# motherboard.net
KiCad netlist of a schematic drawn in EAGLE
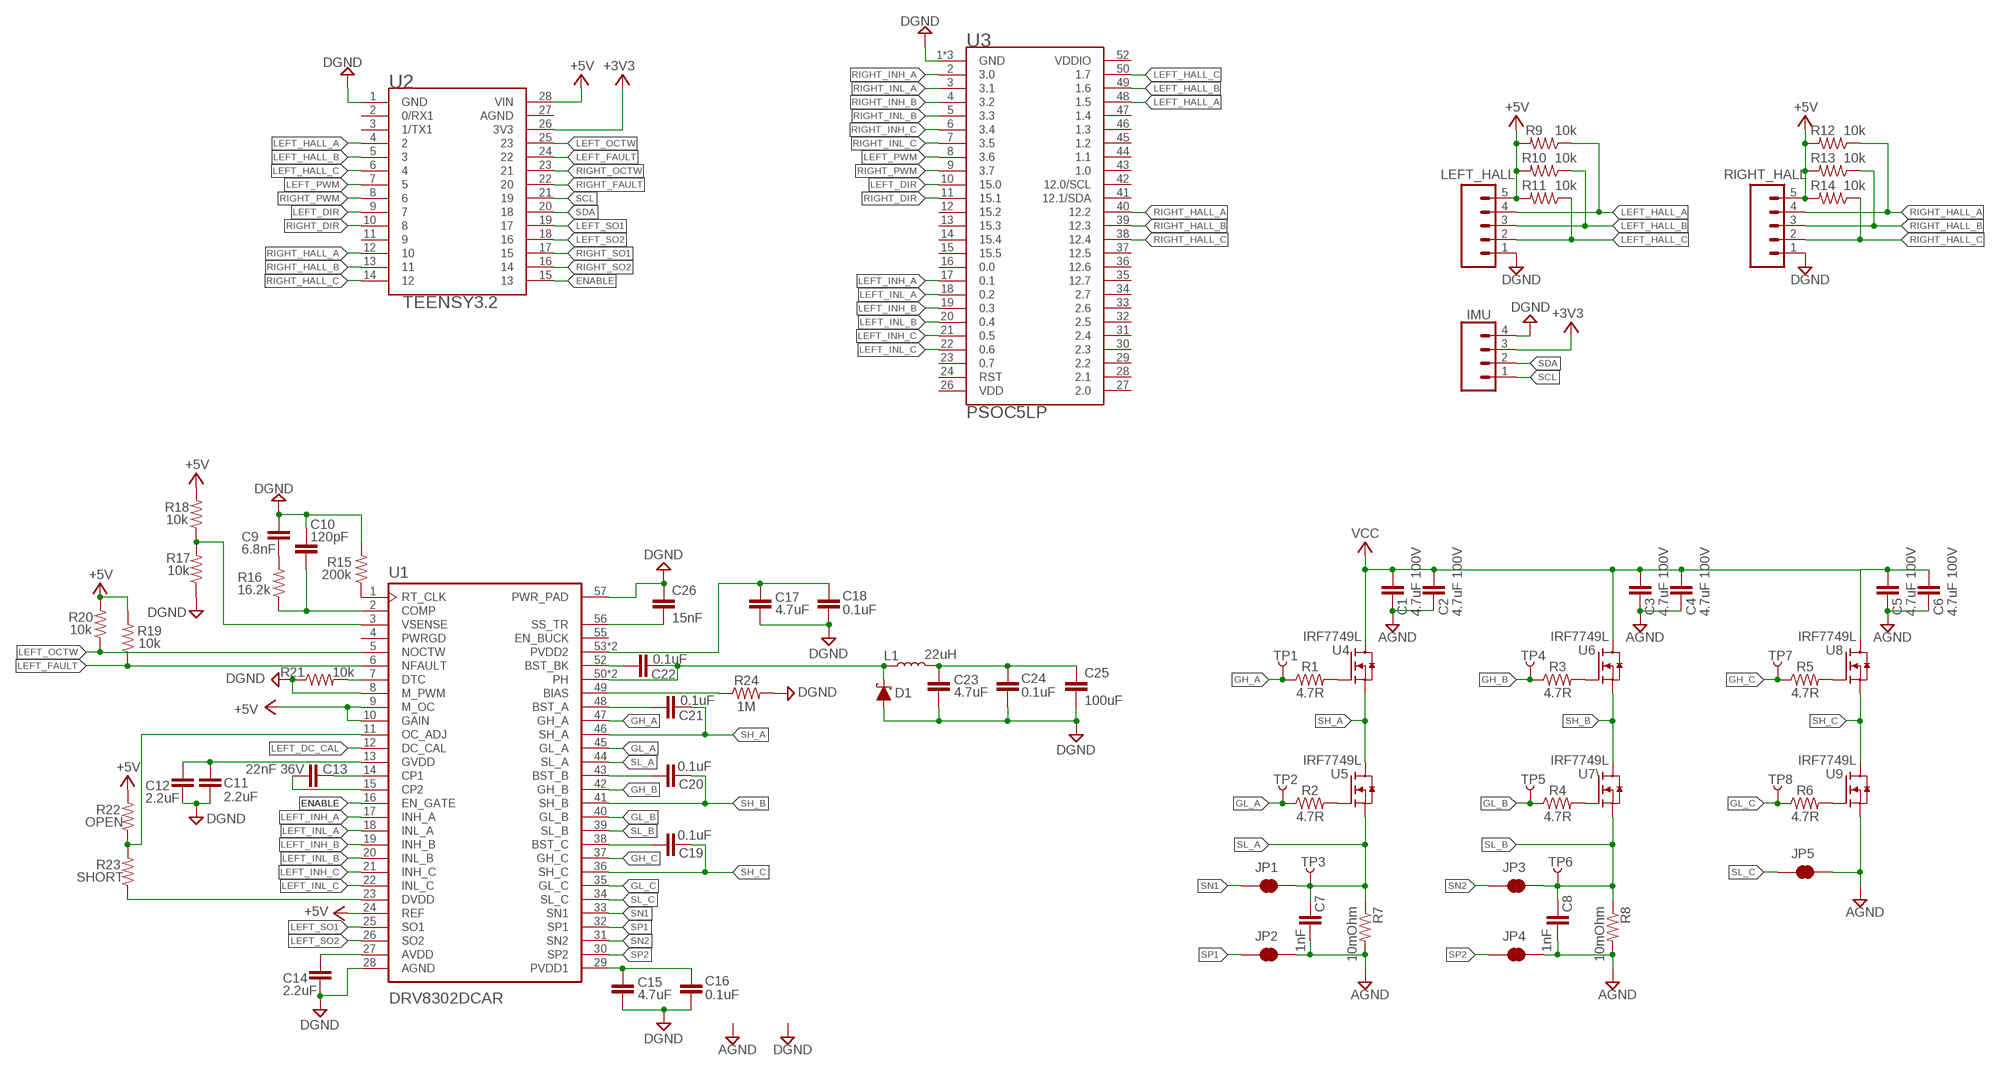
[diagram p0: schematic, sheet 1]

(export (version "E")
  (design (tool "Eeschema 10.0.6"))
  (components
    (comp (ref "C1")
      (value "4.7uF 100V")
      (footprint "eagle-import:1210")
      (libsource (lib "eagle-import") (part "10UF-1210-50V-20%"))
    )
    (comp (ref "C2")
      (value "4.7uF 100V")
      (footprint "eagle-import:1210")
      (libsource (lib "eagle-import") (part "10UF-1210-50V-20%"))
    )
    (comp (ref "C3")
      (value "4.7uF 100V")
      (footprint "eagle-import:1210")
      (libsource (lib "eagle-import") (part "10UF-1210-50V-20%"))
    )
    (comp (ref "C4")
      (value "4.7uF 100V")
      (footprint "eagle-import:1210")
      (libsource (lib "eagle-import") (part "10UF-1210-50V-20%"))
    )
    (comp (ref "C5")
      (value "4.7uF 100V")
      (footprint "eagle-import:1210")
      (libsource (lib "eagle-import") (part "10UF-1210-50V-20%"))
    )
    (comp (ref "C6")
      (value "4.7uF 100V")
      (footprint "eagle-import:1210")
      (libsource (lib "eagle-import") (part "10UF-1210-50V-20%"))
    )
    (comp (ref "C7")
      (value "1nF")
      (footprint "eagle-import:0603")
      (libsource (lib "eagle-import") (part "1.0NF/1000PF-0603-50V-10%"))
    )
    (comp (ref "C8")
      (value "1nF")
      (footprint "eagle-import:0603")
      (libsource (lib "eagle-import") (part "1.0NF/1000PF-0603-50V-10%"))
    )
    (comp (ref "C9")
      (value "6.8nF")
      (footprint "eagle-import:0603")
      (libsource (lib "eagle-import") (part "100PF-0603-50V-5%"))
    )
    (comp (ref "C10")
      (value "120pF")
      (footprint "eagle-import:0603")
      (libsource (lib "eagle-import") (part "100PF-0603-50V-5%"))
    )
    (comp (ref "C11")
      (value "2.2uF")
      (footprint "eagle-import:0805")
      (libsource (lib "eagle-import") (part "2.2UF-0805-25V-(+80/-20%)"))
    )
    (comp (ref "C12")
      (value "2.2uF")
      (footprint "eagle-import:0805")
      (libsource (lib "eagle-import") (part "2.2UF-0805-25V-(+80/-20%)"))
    )
    (comp (ref "C13")
      (value "22nF 36V")
      (footprint "eagle-import:0603")
      (libsource (lib "eagle-import") (part "22NF/22,000PF-0603-50V-10%"))
    )
    (comp (ref "C14")
      (value "2.2uF")
      (footprint "eagle-import:0805")
      (libsource (lib "eagle-import") (part "2.2UF-0805-25V-(+80/-20%)"))
    )
    (comp (ref "C15")
      (value "4.7uF")
      (footprint "eagle-import:0603")
      (libsource (lib "eagle-import") (part "4.7UF-0603-35V-(20%)"))
    )
    (comp (ref "C16")
      (value "0.1uF")
      (footprint "eagle-import:0603")
      (libsource (lib "eagle-import") (part "0.1UF-0603-25V-(+80/-20%)"))
    )
    (comp (ref "C17")
      (value "4.7uF")
      (footprint "eagle-import:0603")
      (libsource (lib "eagle-import") (part "4.7UF-0603-35V-(20%)"))
    )
    (comp (ref "C18")
      (value "0.1uF")
      (footprint "eagle-import:0603")
      (libsource (lib "eagle-import") (part "0.1UF-0603-25V-(+80/-20%)"))
    )
    (comp (ref "C19")
      (value "0.1uF")
      (footprint "eagle-import:0603")
      (libsource (lib "eagle-import") (part "0.1UF-0603-25V-(+80/-20%)"))
    )
    (comp (ref "C20")
      (value "0.1uF")
      (footprint "eagle-import:0603")
      (libsource (lib "eagle-import") (part "0.1UF-0603-25V-(+80/-20%)"))
    )
    (comp (ref "C21")
      (value "0.1uF")
      (footprint "eagle-import:0603")
      (libsource (lib "eagle-import") (part "0.1UF-0603-25V-(+80/-20%)"))
    )
    (comp (ref "C22")
      (value "0.1uF")
      (footprint "eagle-import:0603")
      (libsource (lib "eagle-import") (part "0.1UF-0603-25V-(+80/-20%)"))
    )
    (comp (ref "C23")
      (value "4.7uF")
      (footprint "eagle-import:0603")
      (libsource (lib "eagle-import") (part "4.7UF-0603-35V-(20%)"))
    )
    (comp (ref "C24")
      (value "0.1uF")
      (footprint "eagle-import:0603")
      (libsource (lib "eagle-import") (part "0.1UF-0603-25V-(+80/-20%)"))
    )
    (comp (ref "C25")
      (value "100uF")
      (footprint "eagle-import:1210")
      (libsource (lib "eagle-import") (part "100UF6.3V20%(1210)"))
    )
    (comp (ref "C26")
      (value "15nF")
      (footprint "eagle-import:0603")
      (libsource (lib "eagle-import") (part "10NF-0603-50V-10%"))
    )
    (comp (ref "D1")
      (value "NRVBA2H100T3G")
      (footprint "eagle-import:SMA-DIODE")
      (libsource (lib "eagle-import") (part "DIODE-SCHOTTKY-SS14"))
    )
    (comp (ref "IMU")
      (value "SSM-104-L-SV")
      (footprint "eagle-import:SAMTEC-SSM-104-X-SV")
      (libsource (lib "eagle-import") (part "SSM-104-L-SV"))
    )
    (comp (ref "JP1")
      (value "JUMPER-SMT_2_NC_TRACE_NO-SILK")
      (footprint "eagle-import:SMT-JUMPER_2_NC_TRACE_NO-SILK")
      (libsource (lib "eagle-import") (part "JUMPER-SMT_2_NC_TRACE_NO-SILK"))
    )
    (comp (ref "JP2")
      (value "JUMPER-SMT_2_NC_TRACE_NO-SILK")
      (footprint "eagle-import:SMT-JUMPER_2_NC_TRACE_NO-SILK")
      (libsource (lib "eagle-import") (part "JUMPER-SMT_2_NC_TRACE_NO-SILK"))
    )
    (comp (ref "JP3")
      (value "JUMPER-SMT_2_NC_TRACE_NO-SILK")
      (footprint "eagle-import:SMT-JUMPER_2_NC_TRACE_NO-SILK")
      (libsource (lib "eagle-import") (part "JUMPER-SMT_2_NC_TRACE_NO-SILK"))
    )
    (comp (ref "JP4")
      (value "JUMPER-SMT_2_NC_TRACE_NO-SILK")
      (footprint "eagle-import:SMT-JUMPER_2_NC_TRACE_NO-SILK")
      (libsource (lib "eagle-import") (part "JUMPER-SMT_2_NC_TRACE_NO-SILK"))
    )
    (comp (ref "JP5")
      (value "JUMPER-SMT_2_NC_TRACE_NO-SILK")
      (footprint "eagle-import:SMT-JUMPER_2_NC_TRACE_NO-SILK")
      (libsource (lib "eagle-import") (part "JUMPER-SMT_2_NC_TRACE_NO-SILK"))
    )
    (comp (ref "L1")
      (value "22uH")
      (footprint "eagle-import:LQH43")
      (libsource (lib "eagle-import") (part "LQH43MN330J03L"))
    )
    (comp (ref "LEFT_HALL")
      (value "CONN_05")
      (footprint "eagle-import:1X05")
      (libsource (lib "eagle-import") (part "CONN_05"))
    )
    (comp (ref "R1")
      (value "4.7R")
      (footprint "eagle-import:0603")
      (libsource (lib "eagle-import") (part "2.0KOHM-0603-1/10W-5%"))
    )
    (comp (ref "R2")
      (value "4.7R")
      (footprint "eagle-import:0603")
      (libsource (lib "eagle-import") (part "2.0KOHM-0603-1/10W-5%"))
    )
    (comp (ref "R3")
      (value "4.7R")
      (footprint "eagle-import:0603")
      (libsource (lib "eagle-import") (part "2.0KOHM-0603-1/10W-5%"))
    )
    (comp (ref "R4")
      (value "4.7R")
      (footprint "eagle-import:0603")
      (libsource (lib "eagle-import") (part "2.0KOHM-0603-1/10W-5%"))
    )
    (comp (ref "R5")
      (value "4.7R")
      (footprint "eagle-import:0603")
      (libsource (lib "eagle-import") (part "2.0KOHM-0603-1/10W-5%"))
    )
    (comp (ref "R6")
      (value "4.7R")
      (footprint "eagle-import:0603")
      (libsource (lib "eagle-import") (part "2.0KOHM-0603-1/10W-5%"))
    )
    (comp (ref "R7")
      (value "10mOhm")
      (footprint "eagle-import:R2512")
      (libsource (lib "eagle-import") (part "R-US_R2512"))
    )
    (comp (ref "R8")
      (value "10mOhm")
      (footprint "eagle-import:R2512")
      (libsource (lib "eagle-import") (part "R-US_R2512"))
    )
    (comp (ref "R9")
      (value "10k")
      (footprint "eagle-import:0603")
      (libsource (lib "eagle-import") (part "10KOHM-0603-1/10W-1%"))
    )
    (comp (ref "R10")
      (value "10k")
      (footprint "eagle-import:0603")
      (libsource (lib "eagle-import") (part "10KOHM-0603-1/10W-1%"))
    )
    (comp (ref "R11")
      (value "10k")
      (footprint "eagle-import:0603")
      (libsource (lib "eagle-import") (part "10KOHM-0603-1/10W-1%"))
    )
    (comp (ref "R12")
      (value "10k")
      (footprint "eagle-import:0603")
      (libsource (lib "eagle-import") (part "10KOHM-0603-1/10W-1%"))
    )
    (comp (ref "R13")
      (value "10k")
      (footprint "eagle-import:0603")
      (libsource (lib "eagle-import") (part "10KOHM-0603-1/10W-1%"))
    )
    (comp (ref "R14")
      (value "10k")
      (footprint "eagle-import:0603")
      (libsource (lib "eagle-import") (part "10KOHM-0603-1/10W-1%"))
    )
    (comp (ref "R15")
      (value "200k")
      (footprint "eagle-import:0603")
      (libsource (lib "eagle-import") (part "200KOHM-0603-1/10W-1%"))
    )
    (comp (ref "R16")
      (value "16.2k")
      (footprint "eagle-import:0603")
      (libsource (lib "eagle-import") (part "16.2KOHM-0603-1/10W-1%"))
    )
    (comp (ref "R17")
      (value "10k")
      (footprint "eagle-import:0603")
      (libsource (lib "eagle-import") (part "10KOHM-0603-1/10W-1%"))
    )
    (comp (ref "R18")
      (value "10k")
      (footprint "eagle-import:0603")
      (libsource (lib "eagle-import") (part "10KOHM-0603-1/10W-1%"))
    )
    (comp (ref "R19")
      (value "10k")
      (footprint "eagle-import:0603")
      (libsource (lib "eagle-import") (part "10KOHM-0603-1/10W-1%"))
    )
    (comp (ref "R20")
      (value "10k")
      (footprint "eagle-import:0603")
      (libsource (lib "eagle-import") (part "10KOHM-0603-1/10W-1%"))
    )
    (comp (ref "R21")
      (value "10k")
      (footprint "eagle-import:0603")
      (libsource (lib "eagle-import") (part "10KOHM-0603-1/10W-1%"))
    )
    (comp (ref "R22")
      (value "OPEN")
      (footprint "eagle-import:0603")
      (libsource (lib "eagle-import") (part "10KOHM-0603-1/10W-1%"))
    )
    (comp (ref "R23")
      (value "SHORT")
      (footprint "eagle-import:0603")
      (libsource (lib "eagle-import") (part "10KOHM-0603-1/10W-1%"))
    )
    (comp (ref "R24")
      (value "1M")
      (footprint "eagle-import:0603")
      (libsource (lib "eagle-import") (part "1MOHM-0603-1/4W-5%"))
    )
    (comp (ref "RIGHT_HALL")
      (value "CONN_05")
      (footprint "eagle-import:1X05")
      (libsource (lib "eagle-import") (part "CONN_05"))
    )
    (comp (ref "TP1")
      (value "TEST-POINT3")
      (footprint "eagle-import:PAD.03X.03")
      (libsource (lib "eagle-import") (part "TEST-POINT3"))
    )
    (comp (ref "TP2")
      (value "TEST-POINT3")
      (footprint "eagle-import:PAD.03X.03")
      (libsource (lib "eagle-import") (part "TEST-POINT3"))
    )
    (comp (ref "TP3")
      (value "TEST-POINT3")
      (footprint "eagle-import:PAD.03X.03")
      (libsource (lib "eagle-import") (part "TEST-POINT3"))
    )
    (comp (ref "TP4")
      (value "TEST-POINT3")
      (footprint "eagle-import:PAD.03X.03")
      (libsource (lib "eagle-import") (part "TEST-POINT3"))
    )
    (comp (ref "TP5")
      (value "TEST-POINT3")
      (footprint "eagle-import:PAD.03X.03")
      (libsource (lib "eagle-import") (part "TEST-POINT3"))
    )
    (comp (ref "TP6")
      (value "TEST-POINT3")
      (footprint "eagle-import:PAD.03X.03")
      (libsource (lib "eagle-import") (part "TEST-POINT3"))
    )
    (comp (ref "TP7")
      (value "TEST-POINT3")
      (footprint "eagle-import:PAD.03X.03")
      (libsource (lib "eagle-import") (part "TEST-POINT3"))
    )
    (comp (ref "TP8")
      (value "TEST-POINT3")
      (footprint "eagle-import:PAD.03X.03")
      (libsource (lib "eagle-import") (part "TEST-POINT3"))
    )
    (comp (ref "U1")
      (value "DRV8302DCAR")
      (footprint "eagle-import:SOP50P810X120-57N")
      (fields (field (name "MF") "Texas Instruments"))
      (libsource (lib "eagle-import") (part "DRV8302DCAR"))
    )
    (comp (ref "U2")
      (value "TEENSY3.2")
      (footprint "eagle-import:TEENSY3.2")
      (libsource (lib "eagle-import") (part "TEENSY3.2"))
    )
    (comp (ref "U3")
      (value "PSOC5LP")
      (footprint "eagle-import:PSOC5LP")
      (libsource (lib "eagle-import") (part "PSOC5LP"))
    )
    (comp (ref "U4")
      (value "IRF7749L")
      (footprint "eagle-import:TRANS_AUIRF8739L2TR")
      (libsource (lib "eagle-import") (part "IRF7749L"))
    )
    (comp (ref "U5")
      (value "IRF7749L")
      (footprint "eagle-import:TRANS_AUIRF8739L2TR")
      (libsource (lib "eagle-import") (part "IRF7749L"))
    )
    (comp (ref "U6")
      (value "IRF7749L")
      (footprint "eagle-import:TRANS_AUIRF8739L2TR")
      (libsource (lib "eagle-import") (part "IRF7749L"))
    )
    (comp (ref "U7\\")
      (value "IRF7749L")
      (footprint "eagle-import:TRANS_AUIRF8739L2TR")
      (libsource (lib "eagle-import") (part "IRF7749L"))
    )
    (comp (ref "U8")
      (value "IRF7749L")
      (footprint "eagle-import:TRANS_AUIRF8739L2TR")
      (libsource (lib "eagle-import") (part "IRF7749L"))
    )
    (comp (ref "U9")
      (value "IRF7749L")
      (footprint "eagle-import:TRANS_AUIRF8739L2TR")
      (libsource (lib "eagle-import") (part "IRF7749L"))
    )
  )
  (nets
    (net (code "1") (name "+3V3") (class "Default")
      (node (ref "IMU") (pin "3") (pinfunction "3_3") (pintype "passive"))
      (node (ref "U2") (pin "26") (pinfunction "3V3_26") (pintype "bidirectional"))
    )
    (net (code "2") (name "+5V") (class "Default")
      (node (ref "LEFT_HALL") (pin "5") (pinfunction "5_5") (pintype "passive"))
      (node (ref "R10") (pin "2") (pinfunction "2_2") (pintype "passive"))
      (node (ref "R11") (pin "2") (pinfunction "2_2") (pintype "passive"))
      (node (ref "R12") (pin "2") (pinfunction "2_2") (pintype "passive"))
      (node (ref "R13") (pin "2") (pinfunction "2_2") (pintype "passive"))
      (node (ref "R14") (pin "2") (pinfunction "2_2") (pintype "passive"))
      (node (ref "R18") (pin "2") (pinfunction "2_2") (pintype "passive"))
      (node (ref "R19") (pin "2") (pinfunction "2_2") (pintype "passive"))
      (node (ref "R20") (pin "2") (pinfunction "2_2") (pintype "passive"))
      (node (ref "R22") (pin "2") (pinfunction "2_2") (pintype "passive"))
      (node (ref "R9") (pin "2") (pinfunction "2_2") (pintype "passive"))
      (node (ref "RIGHT_HALL") (pin "5") (pinfunction "5_5") (pintype "passive"))
      (node (ref "U1") (pin "10") (pinfunction "GAIN_10") (pintype "output"))
      (node (ref "U1") (pin "24") (pinfunction "REF_24") (pintype "input"))
      (node (ref "U1") (pin "9") (pinfunction "M_OC_9") (pintype "input"))
      (node (ref "U2") (pin "28") (pinfunction "VIN_28") (pintype "bidirectional"))
    )
    (net (code "3") (name "AGND") (class "Default")
      (node (ref "C1") (pin "2") (pinfunction "2_2") (pintype "passive"))
      (node (ref "C2") (pin "2") (pinfunction "2_2") (pintype "passive"))
      (node (ref "C3") (pin "2") (pinfunction "2_2") (pintype "passive"))
      (node (ref "C4") (pin "2") (pinfunction "2_2") (pintype "passive"))
      (node (ref "C5") (pin "2") (pinfunction "2_2") (pintype "passive"))
      (node (ref "C6") (pin "2") (pinfunction "2_2") (pintype "passive"))
      (node (ref "C7") (pin "2") (pinfunction "2_2") (pintype "passive"))
      (node (ref "C8") (pin "2") (pinfunction "2_2") (pintype "passive"))
      (node (ref "JP2") (pin "2") (pinfunction "2_2") (pintype "passive"))
      (node (ref "JP4") (pin "2") (pinfunction "2_2") (pintype "passive"))
      (node (ref "JP5") (pin "2") (pinfunction "2_2") (pintype "passive"))
      (node (ref "R7") (pin "2") (pinfunction "2_2") (pintype "passive"))
      (node (ref "R8") (pin "2") (pinfunction "2_2") (pintype "passive"))
      (node (ref "U9") (pin "10") (pinfunction "S_10") (pintype "passive"))
      (node (ref "U9") (pin "11") (pinfunction "S_11") (pintype "passive"))
      (node (ref "U9") (pin "4") (pinfunction "S_4") (pintype "passive"))
      (node (ref "U9") (pin "5") (pinfunction "S_5") (pintype "passive"))
      (node (ref "U9") (pin "6") (pinfunction "S_6") (pintype "passive"))
      (node (ref "U9") (pin "7") (pinfunction "S_7") (pintype "passive"))
      (node (ref "U9") (pin "8") (pinfunction "S_8") (pintype "passive"))
      (node (ref "U9") (pin "9") (pinfunction "S_9") (pintype "passive"))
    )
    (net (code "4") (name "DGND") (class "Default")
      (node (ref "C10") (pin "1") (pinfunction "1_1") (pintype "passive"))
      (node (ref "C11") (pin "2") (pinfunction "2_2") (pintype "passive"))
      (node (ref "C12") (pin "2") (pinfunction "2_2") (pintype "passive"))
      (node (ref "C14") (pin "2") (pinfunction "2_2") (pintype "passive"))
      (node (ref "C15") (pin "2") (pinfunction "2_2") (pintype "passive"))
      (node (ref "C16") (pin "2") (pinfunction "2_2") (pintype "passive"))
      (node (ref "C17") (pin "2") (pinfunction "2_2") (pintype "passive"))
      (node (ref "C18") (pin "2") (pinfunction "2_2") (pintype "passive"))
      (node (ref "C23") (pin "2") (pinfunction "2_2") (pintype "passive"))
      (node (ref "C24") (pin "2") (pinfunction "2_2") (pintype "passive"))
      (node (ref "C25") (pin "2") (pinfunction "2_2") (pintype "passive"))
      (node (ref "C26") (pin "1") (pinfunction "1_1") (pintype "passive"))
      (node (ref "C9") (pin "1") (pinfunction "1_1") (pintype "passive"))
      (node (ref "D1") (pin "A") (pinfunction "A_A") (pintype "passive"))
      (node (ref "IMU") (pin "4") (pinfunction "4_4") (pintype "passive"))
      (node (ref "LEFT_HALL") (pin "1") (pinfunction "1_1") (pintype "passive"))
      (node (ref "R15") (pin "2") (pinfunction "2_2") (pintype "passive"))
      (node (ref "R17") (pin "1") (pinfunction "1_1") (pintype "passive"))
      (node (ref "R21") (pin "1") (pinfunction "1_1") (pintype "passive"))
      (node (ref "R24") (pin "2") (pinfunction "2_2") (pintype "passive"))
      (node (ref "RIGHT_HALL") (pin "1") (pinfunction "1_1") (pintype "passive"))
      (node (ref "U1") (pin "28") (pinfunction "AGND_28") (pintype "power_in"))
      (node (ref "U1") (pin "57") (pinfunction "PWR_PAD_57") (pintype "power_in"))
      (node (ref "U1") (pin "8") (pinfunction "M_PWM_8") (pintype "input"))
      (node (ref "U2") (pin "1") (pinfunction "GND_1") (pintype "bidirectional"))
      (node (ref "U3") (pin "1") (pinfunction "GND_1") (pintype "bidirectional"))
      (node (ref "U3") (pin "25") (pinfunction "GND_25") (pintype "bidirectional"))
      (node (ref "U3") (pin "51") (pinfunction "GND_51") (pintype "bidirectional"))
    )
    (net (code "5") (name "ENABLE") (class "Default")
      (node (ref "U1") (pin "16") (pinfunction "EN_GATE_16") (pintype "input"))
      (node (ref "U2") (pin "15") (pinfunction "13_15") (pintype "bidirectional"))
    )
    (net (code "6") (name "GH_A") (class "Default")
      (node (ref "R1") (pin "1") (pinfunction "1_1") (pintype "passive"))
      (node (ref "TP1") (pin "P$1") (pinfunction "1_P$1") (pintype "bidirectional"))
      (node (ref "U1") (pin "47") (pinfunction "GH_A_47") (pintype "output"))
    )
    (net (code "7") (name "GH_B") (class "Default")
      (node (ref "R3") (pin "1") (pinfunction "1_1") (pintype "passive"))
      (node (ref "TP4") (pin "P$1") (pinfunction "1_P$1") (pintype "bidirectional"))
      (node (ref "U1") (pin "42") (pinfunction "GH_B_42") (pintype "output"))
    )
    (net (code "8") (name "GH_C") (class "Default")
      (node (ref "R5") (pin "1") (pinfunction "1_1") (pintype "passive"))
      (node (ref "TP7") (pin "P$1") (pinfunction "1_P$1") (pintype "bidirectional"))
      (node (ref "U1") (pin "37") (pinfunction "GH_C_37") (pintype "output"))
    )
    (net (code "9") (name "GL_A") (class "Default")
      (node (ref "R2") (pin "1") (pinfunction "1_1") (pintype "passive"))
      (node (ref "TP2") (pin "P$1") (pinfunction "1_P$1") (pintype "bidirectional"))
      (node (ref "U1") (pin "45") (pinfunction "GL_A_45") (pintype "output"))
    )
    (net (code "10") (name "GL_B") (class "Default")
      (node (ref "R4") (pin "1") (pinfunction "1_1") (pintype "passive"))
      (node (ref "TP5") (pin "P$1") (pinfunction "1_P$1") (pintype "bidirectional"))
      (node (ref "U1") (pin "40") (pinfunction "GL_B_40") (pintype "output"))
    )
    (net (code "11") (name "GL_C") (class "Default")
      (node (ref "R6") (pin "1") (pinfunction "1_1") (pintype "passive"))
      (node (ref "TP8") (pin "P$1") (pinfunction "1_P$1") (pintype "bidirectional"))
      (node (ref "U1") (pin "35") (pinfunction "GL_C_35") (pintype "output"))
    )
    (net (code "12") (name "LEFT_DC_CAL") (class "Default")
      (node (ref "U1") (pin "12") (pinfunction "DC_CAL_12") (pintype "input"))
    )
    (net (code "13") (name "LEFT_DIR") (class "Default")
      (node (ref "U2") (pin "9") (pinfunction "7_9") (pintype "bidirectional"))
      (node (ref "U3") (pin "10") (pinfunction "15.0_10") (pintype "bidirectional"))
    )
    (net (code "14") (name "LEFT_FAULT") (class "Default")
      (node (ref "R19") (pin "1") (pinfunction "1_1") (pintype "passive"))
      (node (ref "U1") (pin "6") (pinfunction "NFAULT_6") (pintype "output"))
      (node (ref "U2") (pin "24") (pinfunction "22_24") (pintype "bidirectional"))
    )
    (net (code "15") (name "LEFT_HALL_A") (class "Default")
      (node (ref "LEFT_HALL") (pin "4") (pinfunction "4_4") (pintype "passive"))
      (node (ref "R9") (pin "1") (pinfunction "1_1") (pintype "passive"))
      (node (ref "U2") (pin "4") (pinfunction "2_4") (pintype "bidirectional"))
      (node (ref "U3") (pin "48") (pinfunction "1.5_48") (pintype "bidirectional"))
    )
    (net (code "16") (name "LEFT_HALL_B") (class "Default")
      (node (ref "LEFT_HALL") (pin "3") (pinfunction "3_3") (pintype "passive"))
      (node (ref "R10") (pin "1") (pinfunction "1_1") (pintype "passive"))
      (node (ref "U2") (pin "5") (pinfunction "3_5") (pintype "bidirectional"))
      (node (ref "U3") (pin "49") (pinfunction "1.6_49") (pintype "bidirectional"))
    )
    (net (code "17") (name "LEFT_HALL_C") (class "Default")
      (node (ref "LEFT_HALL") (pin "2") (pinfunction "2_2") (pintype "passive"))
      (node (ref "R11") (pin "1") (pinfunction "1_1") (pintype "passive"))
      (node (ref "U2") (pin "6") (pinfunction "4_6") (pintype "bidirectional"))
      (node (ref "U3") (pin "50") (pinfunction "1.7_50") (pintype "bidirectional"))
    )
    (net (code "18") (name "LEFT_INH_A") (class "Default")
      (node (ref "U1") (pin "17") (pinfunction "INH_A_17") (pintype "input"))
      (node (ref "U3") (pin "17") (pinfunction "0.1_17") (pintype "bidirectional"))
    )
    (net (code "19") (name "LEFT_INH_B") (class "Default")
      (node (ref "U1") (pin "19") (pinfunction "INH_B_19") (pintype "input"))
      (node (ref "U3") (pin "19") (pinfunction "0.3_19") (pintype "bidirectional"))
    )
    (net (code "20") (name "LEFT_INH_C") (class "Default")
      (node (ref "U1") (pin "21") (pinfunction "INH_C_21") (pintype "input"))
      (node (ref "U3") (pin "21") (pinfunction "0.5_21") (pintype "bidirectional"))
    )
    (net (code "21") (name "LEFT_INL_A") (class "Default")
      (node (ref "U1") (pin "18") (pinfunction "INL_A_18") (pintype "input"))
      (node (ref "U3") (pin "18") (pinfunction "0.2_18") (pintype "bidirectional"))
    )
    (net (code "22") (name "LEFT_INL_B") (class "Default")
      (node (ref "U1") (pin "20") (pinfunction "INL_B_20") (pintype "input"))
      (node (ref "U3") (pin "20") (pinfunction "0.4_20") (pintype "bidirectional"))
    )
    (net (code "23") (name "LEFT_INL_C") (class "Default")
      (node (ref "U1") (pin "22") (pinfunction "INL_C_22") (pintype "input"))
      (node (ref "U3") (pin "22") (pinfunction "0.6_22") (pintype "bidirectional"))
    )
    (net (code "24") (name "LEFT_OCTW") (class "Default")
      (node (ref "R20") (pin "1") (pinfunction "1_1") (pintype "passive"))
      (node (ref "U1") (pin "5") (pinfunction "NOCTW_5") (pintype "output"))
      (node (ref "U2") (pin "25") (pinfunction "23_25") (pintype "bidirectional"))
    )
    (net (code "25") (name "LEFT_PWM") (class "Default")
      (node (ref "U2") (pin "7") (pinfunction "5_7") (pintype "bidirectional"))
      (node (ref "U3") (pin "8") (pinfunction "3.6_8") (pintype "bidirectional"))
    )
    (net (code "26") (name "LEFT_SO1") (class "Default")
      (node (ref "U1") (pin "25") (pinfunction "SO1_25") (pintype "output"))
      (node (ref "U2") (pin "19") (pinfunction "17_19") (pintype "bidirectional"))
    )
    (net (code "27") (name "LEFT_SO2") (class "Default")
      (node (ref "U1") (pin "26") (pinfunction "SO2_26") (pintype "output"))
      (node (ref "U2") (pin "18") (pinfunction "16_18") (pintype "bidirectional"))
    )
    (net (code "28") (name "Net-(C9-Pad2)") (class "Default")
      (node (ref "C9") (pin "2") (pinfunction "2_2") (pintype "passive"))
      (node (ref "R16") (pin "2") (pinfunction "2_2") (pintype "passive"))
    )
    (net (code "29") (name "Net-(C17-Pad1)") (class "Default")
      (node (ref "C17") (pin "1") (pinfunction "1_1") (pintype "passive"))
      (node (ref "C18") (pin "1") (pinfunction "1_1") (pintype "passive"))
      (node (ref "U1") (pin "53") (pinfunction "PVDD2_53") (pintype "power_in"))
      (node (ref "U1") (pin "54") (pinfunction "PVDD2_54") (pintype "power_in"))
    )
    (net (code "30") (name "Net-(C22-Pad1)") (class "Default")
      (node (ref "C22") (pin "1") (pinfunction "1_1") (pintype "passive"))
      (node (ref "D1") (pin "C") (pinfunction "C_C") (pintype "passive"))
      (node (ref "L1") (pin "1") (pinfunction "1_1") (pintype "passive"))
      (node (ref "U1") (pin "50") (pinfunction "PH_50") (pintype "bidirectional"))
      (node (ref "U1") (pin "51") (pinfunction "PH_51") (pintype "bidirectional"))
    )
    (net (code "31") (name "Net-(C23-Pad1)") (class "Default")
      (node (ref "C23") (pin "1") (pinfunction "1_1") (pintype "passive"))
      (node (ref "C24") (pin "1") (pinfunction "1_1") (pintype "passive"))
      (node (ref "C25") (pin "1") (pinfunction "1_1") (pintype "passive"))
      (node (ref "L1") (pin "2") (pinfunction "2_2") (pintype "passive"))
    )
    (net (code "32") (name "Net-(U1-AVDD)") (class "Default")
      (node (ref "C14") (pin "1") (pinfunction "1_1") (pintype "passive"))
      (node (ref "U1") (pin "27") (pinfunction "AVDD_27") (pintype "power_in"))
    )
    (net (code "33") (name "Net-(U1-BIAS)") (class "Default")
      (node (ref "R24") (pin "1") (pinfunction "1_1") (pintype "passive"))
      (node (ref "U1") (pin "49") (pinfunction "BIAS_49") (pintype "input"))
    )
    (net (code "34") (name "Net-(U1-BST_A)") (class "Default")
      (node (ref "C21") (pin "2") (pinfunction "2_2") (pintype "passive"))
      (node (ref "U1") (pin "48") (pinfunction "BST_A_48") (pintype "power_in"))
    )
    (net (code "35") (name "Net-(U1-BST_B)") (class "Default")
      (node (ref "C20") (pin "2") (pinfunction "2_2") (pintype "passive"))
      (node (ref "U1") (pin "43") (pinfunction "BST_B_43") (pintype "power_in"))
    )
    (net (code "36") (name "Net-(U1-BST_BK)") (class "Default")
      (node (ref "C22") (pin "2") (pinfunction "2_2") (pintype "passive"))
      (node (ref "U1") (pin "52") (pinfunction "BST_BK_52") (pintype "power_in"))
    )
    (net (code "37") (name "Net-(U1-BST_C)") (class "Default")
      (node (ref "C19") (pin "2") (pinfunction "2_2") (pintype "passive"))
      (node (ref "U1") (pin "38") (pinfunction "BST_C_38") (pintype "power_in"))
    )
    (net (code "38") (name "Net-(U1-COMP)") (class "Default")
      (node (ref "C10") (pin "2") (pinfunction "2_2") (pintype "passive"))
      (node (ref "R16") (pin "1") (pinfunction "1_1") (pintype "passive"))
      (node (ref "U1") (pin "2") (pinfunction "COMP_2") (pintype "output"))
    )
    (net (code "39") (name "Net-(U1-CP1)") (class "Default")
      (node (ref "C13") (pin "1") (pinfunction "1_1") (pintype "passive"))
      (node (ref "U1") (pin "14") (pinfunction "CP1_14") (pintype "power_in"))
    )
    (net (code "40") (name "Net-(U1-CP2)") (class "Default")
      (node (ref "C13") (pin "2") (pinfunction "2_2") (pintype "passive"))
      (node (ref "U1") (pin "15") (pinfunction "CP2_15") (pintype "power_in"))
    )
    (net (code "41") (name "Net-(U1-DTC)") (class "Default")
      (node (ref "R21") (pin "2") (pinfunction "2_2") (pintype "passive"))
      (node (ref "U1") (pin "7") (pinfunction "DTC_7") (pintype "input"))
    )
    (net (code "42") (name "Net-(U1-DVDD)") (class "Default")
      (node (ref "R23") (pin "1") (pinfunction "1_1") (pintype "passive"))
      (node (ref "U1") (pin "23") (pinfunction "DVDD_23") (pintype "power_in"))
    )
    (net (code "43") (name "Net-(U1-GVDD)") (class "Default")
      (node (ref "C11") (pin "1") (pinfunction "1_1") (pintype "passive"))
      (node (ref "C12") (pin "1") (pinfunction "1_1") (pintype "passive"))
      (node (ref "U1") (pin "13") (pinfunction "GVDD_13") (pintype "power_in"))
    )
    (net (code "44") (name "Net-(U1-OC_ADJ)") (class "Default")
      (node (ref "R22") (pin "1") (pinfunction "1_1") (pintype "passive"))
      (node (ref "R23") (pin "2") (pinfunction "2_2") (pintype "passive"))
      (node (ref "U1") (pin "11") (pinfunction "OC_ADJ_11") (pintype "input"))
    )
    (net (code "45") (name "Net-(U1-PVDD1)") (class "Default")
      (node (ref "C15") (pin "1") (pinfunction "1_1") (pintype "passive"))
      (node (ref "C16") (pin "1") (pinfunction "1_1") (pintype "passive"))
      (node (ref "U1") (pin "29") (pinfunction "PVDD1_29") (pintype "power_in"))
    )
    (net (code "46") (name "Net-(U1-RT_CLK)") (class "Default")
      (node (ref "R15") (pin "1") (pinfunction "1_1") (pintype "passive"))
      (node (ref "U1") (pin "1") (pinfunction "RT_CLK_1") (pintype "input"))
    )
    (net (code "47") (name "Net-(U1-SS_TR)") (class "Default")
      (node (ref "C26") (pin "2") (pinfunction "2_2") (pintype "passive"))
      (node (ref "U1") (pin "56") (pinfunction "SS_TR_56") (pintype "input"))
    )
    (net (code "48") (name "Net-(U1-VSENSE)") (class "Default")
      (node (ref "R17") (pin "2") (pinfunction "2_2") (pintype "passive"))
      (node (ref "R18") (pin "1") (pinfunction "1_1") (pintype "passive"))
      (node (ref "U1") (pin "3") (pinfunction "VSENSE_3") (pintype "input"))
    )
    (net (code "49") (name "Net-(U4-G)") (class "Default")
      (node (ref "R1") (pin "2") (pinfunction "2_2") (pintype "passive"))
      (node (ref "U4") (pin "12") (pinfunction "G_12") (pintype "passive"))
    )
    (net (code "50") (name "Net-(U5-G)") (class "Default")
      (node (ref "R2") (pin "2") (pinfunction "2_2") (pintype "passive"))
      (node (ref "U5") (pin "12") (pinfunction "G_12") (pintype "passive"))
    )
    (net (code "51") (name "Net-(U6-G)") (class "Default")
      (node (ref "R3") (pin "2") (pinfunction "2_2") (pintype "passive"))
      (node (ref "U6") (pin "12") (pinfunction "G_12") (pintype "passive"))
    )
    (net (code "52") (name "Net-(U7\\-G)") (class "Default")
      (node (ref "R4") (pin "2") (pinfunction "2_2") (pintype "passive"))
      (node (ref "U7\\") (pin "12") (pinfunction "G_12") (pintype "passive"))
    )
    (net (code "53") (name "Net-(U8-G)") (class "Default")
      (node (ref "R5") (pin "2") (pinfunction "2_2") (pintype "passive"))
      (node (ref "U8") (pin "12") (pinfunction "G_12") (pintype "passive"))
    )
    (net (code "54") (name "Net-(U9-G)") (class "Default")
      (node (ref "R6") (pin "2") (pinfunction "2_2") (pintype "passive"))
      (node (ref "U9") (pin "12") (pinfunction "G_12") (pintype "passive"))
    )
    (net (code "55") (name "RIGHT_DIR") (class "Default")
      (node (ref "U2") (pin "10") (pinfunction "8_10") (pintype "bidirectional"))
      (node (ref "U3") (pin "11") (pinfunction "15.1_11") (pintype "bidirectional"))
    )
    (net (code "56") (name "RIGHT_FAULT") (class "Default")
      (node (ref "U2") (pin "22") (pinfunction "20_22") (pintype "bidirectional"))
    )
    (net (code "57") (name "RIGHT_HALL_A") (class "Default")
      (node (ref "R12") (pin "1") (pinfunction "1_1") (pintype "passive"))
      (node (ref "RIGHT_HALL") (pin "4") (pinfunction "4_4") (pintype "passive"))
      (node (ref "U2") (pin "12") (pinfunction "10_12") (pintype "bidirectional"))
      (node (ref "U3") (pin "40") (pinfunction "12.2_40") (pintype "bidirectional"))
    )
    (net (code "58") (name "RIGHT_HALL_B") (class "Default")
      (node (ref "R13") (pin "1") (pinfunction "1_1") (pintype "passive"))
      (node (ref "RIGHT_HALL") (pin "3") (pinfunction "3_3") (pintype "passive"))
      (node (ref "U2") (pin "13") (pinfunction "11_13") (pintype "bidirectional"))
      (node (ref "U3") (pin "39") (pinfunction "12.3_39") (pintype "bidirectional"))
    )
    (net (code "59") (name "RIGHT_HALL_C") (class "Default")
      (node (ref "R14") (pin "1") (pinfunction "1_1") (pintype "passive"))
      (node (ref "RIGHT_HALL") (pin "2") (pinfunction "2_2") (pintype "passive"))
      (node (ref "U2") (pin "14") (pinfunction "12_14") (pintype "bidirectional"))
      (node (ref "U3") (pin "38") (pinfunction "12.4_38") (pintype "bidirectional"))
    )
    (net (code "60") (name "RIGHT_INH_A") (class "Default")
      (node (ref "U3") (pin "2") (pinfunction "3.0_2") (pintype "bidirectional"))
    )
    (net (code "61") (name "RIGHT_INH_B") (class "Default")
      (node (ref "U3") (pin "4") (pinfunction "3.2_4") (pintype "bidirectional"))
    )
    (net (code "62") (name "RIGHT_INH_C") (class "Default")
      (node (ref "U3") (pin "6") (pinfunction "3.4_6") (pintype "bidirectional"))
    )
    (net (code "63") (name "RIGHT_INL_A") (class "Default")
      (node (ref "U3") (pin "3") (pinfunction "3.1_3") (pintype "bidirectional"))
    )
    (net (code "64") (name "RIGHT_INL_B") (class "Default")
      (node (ref "U3") (pin "5") (pinfunction "3.3_5") (pintype "bidirectional"))
    )
    (net (code "65") (name "RIGHT_INL_C") (class "Default")
      (node (ref "U3") (pin "7") (pinfunction "3.5_7") (pintype "bidirectional"))
    )
    (net (code "66") (name "RIGHT_OCTW") (class "Default")
      (node (ref "U2") (pin "23") (pinfunction "21_23") (pintype "bidirectional"))
    )
    (net (code "67") (name "RIGHT_PWM") (class "Default")
      (node (ref "U2") (pin "8") (pinfunction "6_8") (pintype "bidirectional"))
      (node (ref "U3") (pin "9") (pinfunction "3.7_9") (pintype "bidirectional"))
    )
    (net (code "68") (name "RIGHT_SO1") (class "Default")
      (node (ref "U2") (pin "17") (pinfunction "15_17") (pintype "bidirectional"))
    )
    (net (code "69") (name "RIGHT_SO2") (class "Default")
      (node (ref "U2") (pin "16") (pinfunction "14_16") (pintype "bidirectional"))
    )
    (net (code "70") (name "SCL") (class "Default")
      (node (ref "IMU") (pin "1") (pinfunction "1_1") (pintype "passive"))
      (node (ref "U2") (pin "21") (pinfunction "19_21") (pintype "bidirectional"))
    )
    (net (code "71") (name "SDA") (class "Default")
      (node (ref "IMU") (pin "2") (pinfunction "2_2") (pintype "passive"))
      (node (ref "U2") (pin "20") (pinfunction "18_20") (pintype "bidirectional"))
    )
    (net (code "72") (name "SH_A") (class "Default")
      (node (ref "C21") (pin "1") (pinfunction "1_1") (pintype "passive"))
      (node (ref "U1") (pin "46") (pinfunction "SH_A_46") (pintype "input"))
      (node (ref "U4") (pin "10") (pinfunction "S_10") (pintype "passive"))
      (node (ref "U4") (pin "11") (pinfunction "S_11") (pintype "passive"))
      (node (ref "U4") (pin "4") (pinfunction "S_4") (pintype "passive"))
      (node (ref "U4") (pin "5") (pinfunction "S_5") (pintype "passive"))
      (node (ref "U4") (pin "6") (pinfunction "S_6") (pintype "passive"))
      (node (ref "U4") (pin "7") (pinfunction "S_7") (pintype "passive"))
      (node (ref "U4") (pin "8") (pinfunction "S_8") (pintype "passive"))
      (node (ref "U4") (pin "9") (pinfunction "S_9") (pintype "passive"))
      (node (ref "U5") (pin "1") (pinfunction "D_1") (pintype "passive"))
      (node (ref "U5") (pin "13") (pinfunction "D_13") (pintype "passive"))
      (node (ref "U5") (pin "14") (pinfunction "D_14") (pintype "passive"))
      (node (ref "U5") (pin "15") (pinfunction "D_15") (pintype "passive"))
      (node (ref "U5") (pin "2") (pinfunction "D_2") (pintype "passive"))
      (node (ref "U5") (pin "3") (pinfunction "D_3") (pintype "passive"))
    )
    (net (code "73") (name "SH_B") (class "Default")
      (node (ref "C20") (pin "1") (pinfunction "1_1") (pintype "passive"))
      (node (ref "U1") (pin "41") (pinfunction "SH_B_41") (pintype "input"))
      (node (ref "U6") (pin "10") (pinfunction "S_10") (pintype "passive"))
      (node (ref "U6") (pin "11") (pinfunction "S_11") (pintype "passive"))
      (node (ref "U6") (pin "4") (pinfunction "S_4") (pintype "passive"))
      (node (ref "U6") (pin "5") (pinfunction "S_5") (pintype "passive"))
      (node (ref "U6") (pin "6") (pinfunction "S_6") (pintype "passive"))
      (node (ref "U6") (pin "7") (pinfunction "S_7") (pintype "passive"))
      (node (ref "U6") (pin "8") (pinfunction "S_8") (pintype "passive"))
      (node (ref "U6") (pin "9") (pinfunction "S_9") (pintype "passive"))
      (node (ref "U7\\") (pin "1") (pinfunction "D_1") (pintype "passive"))
      (node (ref "U7\\") (pin "13") (pinfunction "D_13") (pintype "passive"))
      (node (ref "U7\\") (pin "14") (pinfunction "D_14") (pintype "passive"))
      (node (ref "U7\\") (pin "15") (pinfunction "D_15") (pintype "passive"))
      (node (ref "U7\\") (pin "2") (pinfunction "D_2") (pintype "passive"))
      (node (ref "U7\\") (pin "3") (pinfunction "D_3") (pintype "passive"))
    )
    (net (code "74") (name "SH_C") (class "Default")
      (node (ref "C19") (pin "1") (pinfunction "1_1") (pintype "passive"))
      (node (ref "U1") (pin "36") (pinfunction "SH_C_36") (pintype "input"))
      (node (ref "U8") (pin "10") (pinfunction "S_10") (pintype "passive"))
      (node (ref "U8") (pin "11") (pinfunction "S_11") (pintype "passive"))
      (node (ref "U8") (pin "4") (pinfunction "S_4") (pintype "passive"))
      (node (ref "U8") (pin "5") (pinfunction "S_5") (pintype "passive"))
      (node (ref "U8") (pin "6") (pinfunction "S_6") (pintype "passive"))
      (node (ref "U8") (pin "7") (pinfunction "S_7") (pintype "passive"))
      (node (ref "U8") (pin "8") (pinfunction "S_8") (pintype "passive"))
      (node (ref "U8") (pin "9") (pinfunction "S_9") (pintype "passive"))
      (node (ref "U9") (pin "1") (pinfunction "D_1") (pintype "passive"))
      (node (ref "U9") (pin "13") (pinfunction "D_13") (pintype "passive"))
      (node (ref "U9") (pin "14") (pinfunction "D_14") (pintype "passive"))
      (node (ref "U9") (pin "15") (pinfunction "D_15") (pintype "passive"))
      (node (ref "U9") (pin "2") (pinfunction "D_2") (pintype "passive"))
      (node (ref "U9") (pin "3") (pinfunction "D_3") (pintype "passive"))
    )
    (net (code "75") (name "SL_A") (class "Default")
      (node (ref "C7") (pin "1") (pinfunction "1_1") (pintype "passive"))
      (node (ref "JP1") (pin "2") (pinfunction "2_2") (pintype "passive"))
      (node (ref "R7") (pin "1") (pinfunction "1_1") (pintype "passive"))
      (node (ref "TP3") (pin "P$1") (pinfunction "1_P$1") (pintype "bidirectional"))
      (node (ref "U1") (pin "44") (pinfunction "SL_A_44") (pintype "input"))
      (node (ref "U5") (pin "10") (pinfunction "S_10") (pintype "passive"))
      (node (ref "U5") (pin "11") (pinfunction "S_11") (pintype "passive"))
      (node (ref "U5") (pin "4") (pinfunction "S_4") (pintype "passive"))
      (node (ref "U5") (pin "5") (pinfunction "S_5") (pintype "passive"))
      (node (ref "U5") (pin "6") (pinfunction "S_6") (pintype "passive"))
      (node (ref "U5") (pin "7") (pinfunction "S_7") (pintype "passive"))
      (node (ref "U5") (pin "8") (pinfunction "S_8") (pintype "passive"))
      (node (ref "U5") (pin "9") (pinfunction "S_9") (pintype "passive"))
    )
    (net (code "76") (name "SL_B") (class "Default")
      (node (ref "C8") (pin "1") (pinfunction "1_1") (pintype "passive"))
      (node (ref "JP3") (pin "2") (pinfunction "2_2") (pintype "passive"))
      (node (ref "R8") (pin "1") (pinfunction "1_1") (pintype "passive"))
      (node (ref "TP6") (pin "P$1") (pinfunction "1_P$1") (pintype "bidirectional"))
      (node (ref "U1") (pin "39") (pinfunction "SL_B_39") (pintype "input"))
      (node (ref "U7\\") (pin "10") (pinfunction "S_10") (pintype "passive"))
      (node (ref "U7\\") (pin "11") (pinfunction "S_11") (pintype "passive"))
      (node (ref "U7\\") (pin "4") (pinfunction "S_4") (pintype "passive"))
      (node (ref "U7\\") (pin "5") (pinfunction "S_5") (pintype "passive"))
      (node (ref "U7\\") (pin "6") (pinfunction "S_6") (pintype "passive"))
      (node (ref "U7\\") (pin "7") (pinfunction "S_7") (pintype "passive"))
      (node (ref "U7\\") (pin "8") (pinfunction "S_8") (pintype "passive"))
      (node (ref "U7\\") (pin "9") (pinfunction "S_9") (pintype "passive"))
    )
    (net (code "77") (name "SL_C") (class "Default")
      (node (ref "JP5") (pin "1") (pinfunction "1_1") (pintype "passive"))
      (node (ref "U1") (pin "34") (pinfunction "SL_C_34") (pintype "input"))
    )
    (net (code "78") (name "SN1") (class "Default")
      (node (ref "JP1") (pin "1") (pinfunction "1_1") (pintype "passive"))
      (node (ref "U1") (pin "33") (pinfunction "SN1_33") (pintype "input"))
    )
    (net (code "79") (name "SN2") (class "Default")
      (node (ref "JP3") (pin "1") (pinfunction "1_1") (pintype "passive"))
      (node (ref "U1") (pin "31") (pinfunction "SN2_31") (pintype "input"))
    )
    (net (code "80") (name "SP1") (class "Default")
      (node (ref "JP2") (pin "1") (pinfunction "1_1") (pintype "passive"))
      (node (ref "U1") (pin "32") (pinfunction "SP1_32") (pintype "input"))
    )
    (net (code "81") (name "SP2") (class "Default")
      (node (ref "JP4") (pin "1") (pinfunction "1_1") (pintype "passive"))
      (node (ref "U1") (pin "30") (pinfunction "SP2_30") (pintype "input"))
    )
    (net (code "82") (name "VCC") (class "Default")
      (node (ref "C1") (pin "1") (pinfunction "1_1") (pintype "passive"))
      (node (ref "C2") (pin "1") (pinfunction "1_1") (pintype "passive"))
      (node (ref "C3") (pin "1") (pinfunction "1_1") (pintype "passive"))
      (node (ref "C4") (pin "1") (pinfunction "1_1") (pintype "passive"))
      (node (ref "C5") (pin "1") (pinfunction "1_1") (pintype "passive"))
      (node (ref "C6") (pin "1") (pinfunction "1_1") (pintype "passive"))
      (node (ref "U4") (pin "1") (pinfunction "D_1") (pintype "passive"))
      (node (ref "U4") (pin "13") (pinfunction "D_13") (pintype "passive"))
      (node (ref "U4") (pin "14") (pinfunction "D_14") (pintype "passive"))
      (node (ref "U4") (pin "15") (pinfunction "D_15") (pintype "passive"))
      (node (ref "U4") (pin "2") (pinfunction "D_2") (pintype "passive"))
      (node (ref "U4") (pin "3") (pinfunction "D_3") (pintype "passive"))
      (node (ref "U6") (pin "1") (pinfunction "D_1") (pintype "passive"))
      (node (ref "U6") (pin "13") (pinfunction "D_13") (pintype "passive"))
      (node (ref "U6") (pin "14") (pinfunction "D_14") (pintype "passive"))
      (node (ref "U6") (pin "15") (pinfunction "D_15") (pintype "passive"))
      (node (ref "U6") (pin "2") (pinfunction "D_2") (pintype "passive"))
      (node (ref "U6") (pin "3") (pinfunction "D_3") (pintype "passive"))
      (node (ref "U8") (pin "1") (pinfunction "D_1") (pintype "passive"))
      (node (ref "U8") (pin "13") (pinfunction "D_13") (pintype "passive"))
      (node (ref "U8") (pin "14") (pinfunction "D_14") (pintype "passive"))
      (node (ref "U8") (pin "15") (pinfunction "D_15") (pintype "passive"))
      (node (ref "U8") (pin "2") (pinfunction "D_2") (pintype "passive"))
      (node (ref "U8") (pin "3") (pinfunction "D_3") (pintype "passive"))
    )
    (net (code "83") (name "unconnected-(U1-EN_BUCK-Pad55)") (class "Default")
      (node (ref "U1") (pin "55") (pinfunction "EN_BUCK_55") (pintype "input"))
    )
    (net (code "84") (name "unconnected-(U1-PWRGD-Pad4)") (class "Default")
      (node (ref "U1") (pin "4") (pinfunction "PWRGD_4") (pintype "input"))
    )
    (net (code "85") (name "unconnected-(U2-0{slash}RX1-Pad2)") (class "Default")
      (node (ref "U2") (pin "2") (pinfunction "0/RX1_2") (pintype "bidirectional"))
    )
    (net (code "86") (name "unconnected-(U2-1{slash}TX1-Pad3)") (class "Default")
      (node (ref "U2") (pin "3") (pinfunction "1/TX1_3") (pintype "bidirectional"))
    )
    (net (code "87") (name "unconnected-(U2-9-Pad11)") (class "Default")
      (node (ref "U2") (pin "11") (pinfunction "9_11") (pintype "bidirectional"))
    )
    (net (code "88") (name "unconnected-(U2-AGND-Pad27)") (class "Default")
      (node (ref "U2") (pin "27") (pinfunction "AGND_27") (pintype "bidirectional"))
    )
    (net (code "89") (name "unconnected-(U3-0.0-Pad16)") (class "Default")
      (node (ref "U3") (pin "16") (pinfunction "0.0_16") (pintype "bidirectional"))
    )
    (net (code "90") (name "unconnected-(U3-0.7-Pad23)") (class "Default")
      (node (ref "U3") (pin "23") (pinfunction "0.7_23") (pintype "bidirectional"))
    )
    (net (code "91") (name "unconnected-(U3-1.0-Pad43)") (class "Default")
      (node (ref "U3") (pin "43") (pinfunction "1.0_43") (pintype "bidirectional"))
    )
    (net (code "92") (name "unconnected-(U3-1.1-Pad44)") (class "Default")
      (node (ref "U3") (pin "44") (pinfunction "1.1_44") (pintype "bidirectional"))
    )
    (net (code "93") (name "unconnected-(U3-1.2-Pad45)") (class "Default")
      (node (ref "U3") (pin "45") (pinfunction "1.2_45") (pintype "bidirectional"))
    )
    (net (code "94") (name "unconnected-(U3-1.3-Pad46)") (class "Default")
      (node (ref "U3") (pin "46") (pinfunction "1.3_46") (pintype "bidirectional"))
    )
    (net (code "95") (name "unconnected-(U3-1.4-Pad47)") (class "Default")
      (node (ref "U3") (pin "47") (pinfunction "1.4_47") (pintype "bidirectional"))
    )
    (net (code "96") (name "unconnected-(U3-2.0-Pad27)") (class "Default")
      (node (ref "U3") (pin "27") (pinfunction "2.0_27") (pintype "bidirectional"))
    )
    (net (code "97") (name "unconnected-(U3-2.1-Pad28)") (class "Default")
      (node (ref "U3") (pin "28") (pinfunction "2.1_28") (pintype "bidirectional"))
    )
    (net (code "98") (name "unconnected-(U3-2.2-Pad29)") (class "Default")
      (node (ref "U3") (pin "29") (pinfunction "2.2_29") (pintype "bidirectional"))
    )
    (net (code "99") (name "unconnected-(U3-2.3-Pad30)") (class "Default")
      (node (ref "U3") (pin "30") (pinfunction "2.3_30") (pintype "bidirectional"))
    )
    (net (code "100") (name "unconnected-(U3-2.4-Pad31)") (class "Default")
      (node (ref "U3") (pin "31") (pinfunction "2.4_31") (pintype "bidirectional"))
    )
    (net (code "101") (name "unconnected-(U3-2.5-Pad32)") (class "Default")
      (node (ref "U3") (pin "32") (pinfunction "2.5_32") (pintype "bidirectional"))
    )
    (net (code "102") (name "unconnected-(U3-2.6-Pad33)") (class "Default")
      (node (ref "U3") (pin "33") (pinfunction "2.6_33") (pintype "bidirectional"))
    )
    (net (code "103") (name "unconnected-(U3-2.7-Pad34)") (class "Default")
      (node (ref "U3") (pin "34") (pinfunction "2.7_34") (pintype "bidirectional"))
    )
    (net (code "104") (name "unconnected-(U3-12.0{slash}SCL-Pad42)") (class "Default")
      (node (ref "U3") (pin "42") (pinfunction "12.0/SCL_42") (pintype "bidirectional"))
    )
    (net (code "105") (name "unconnected-(U3-12.1{slash}SDA-Pad41)") (class "Default")
      (node (ref "U3") (pin "41") (pinfunction "12.1/SDA_41") (pintype "bidirectional"))
    )
    (net (code "106") (name "unconnected-(U3-12.5-Pad37)") (class "Default")
      (node (ref "U3") (pin "37") (pinfunction "12.5_37") (pintype "bidirectional"))
    )
    (net (code "107") (name "unconnected-(U3-12.6-Pad36)") (class "Default")
      (node (ref "U3") (pin "36") (pinfunction "12.6_36") (pintype "bidirectional"))
    )
    (net (code "108") (name "unconnected-(U3-12.7-Pad35)") (class "Default")
      (node (ref "U3") (pin "35") (pinfunction "12.7_35") (pintype "bidirectional"))
    )
    (net (code "109") (name "unconnected-(U3-15.2-Pad12)") (class "Default")
      (node (ref "U3") (pin "12") (pinfunction "15.2_12") (pintype "bidirectional"))
    )
    (net (code "110") (name "unconnected-(U3-15.3-Pad13)") (class "Default")
      (node (ref "U3") (pin "13") (pinfunction "15.3_13") (pintype "bidirectional"))
    )
    (net (code "111") (name "unconnected-(U3-15.4-Pad14)") (class "Default")
      (node (ref "U3") (pin "14") (pinfunction "15.4_14") (pintype "bidirectional"))
    )
    (net (code "112") (name "unconnected-(U3-15.5-Pad15)") (class "Default")
      (node (ref "U3") (pin "15") (pinfunction "15.5_15") (pintype "bidirectional"))
    )
    (net (code "113") (name "unconnected-(U3-RST-Pad24)") (class "Default")
      (node (ref "U3") (pin "24") (pinfunction "RST_24") (pintype "bidirectional"))
    )
    (net (code "114") (name "unconnected-(U3-VDD-Pad26)") (class "Default")
      (node (ref "U3") (pin "26") (pinfunction "VDD_26") (pintype "bidirectional"))
    )
    (net (code "115") (name "unconnected-(U3-VDDIO-Pad52)") (class "Default")
      (node (ref "U3") (pin "52") (pinfunction "VDDIO_52") (pintype "bidirectional"))
    )
  )
)
